# SCH_Plantcare_Module-v3_2024-10-25.net
KiCad netlist of a schematic drawn in EasyEDA
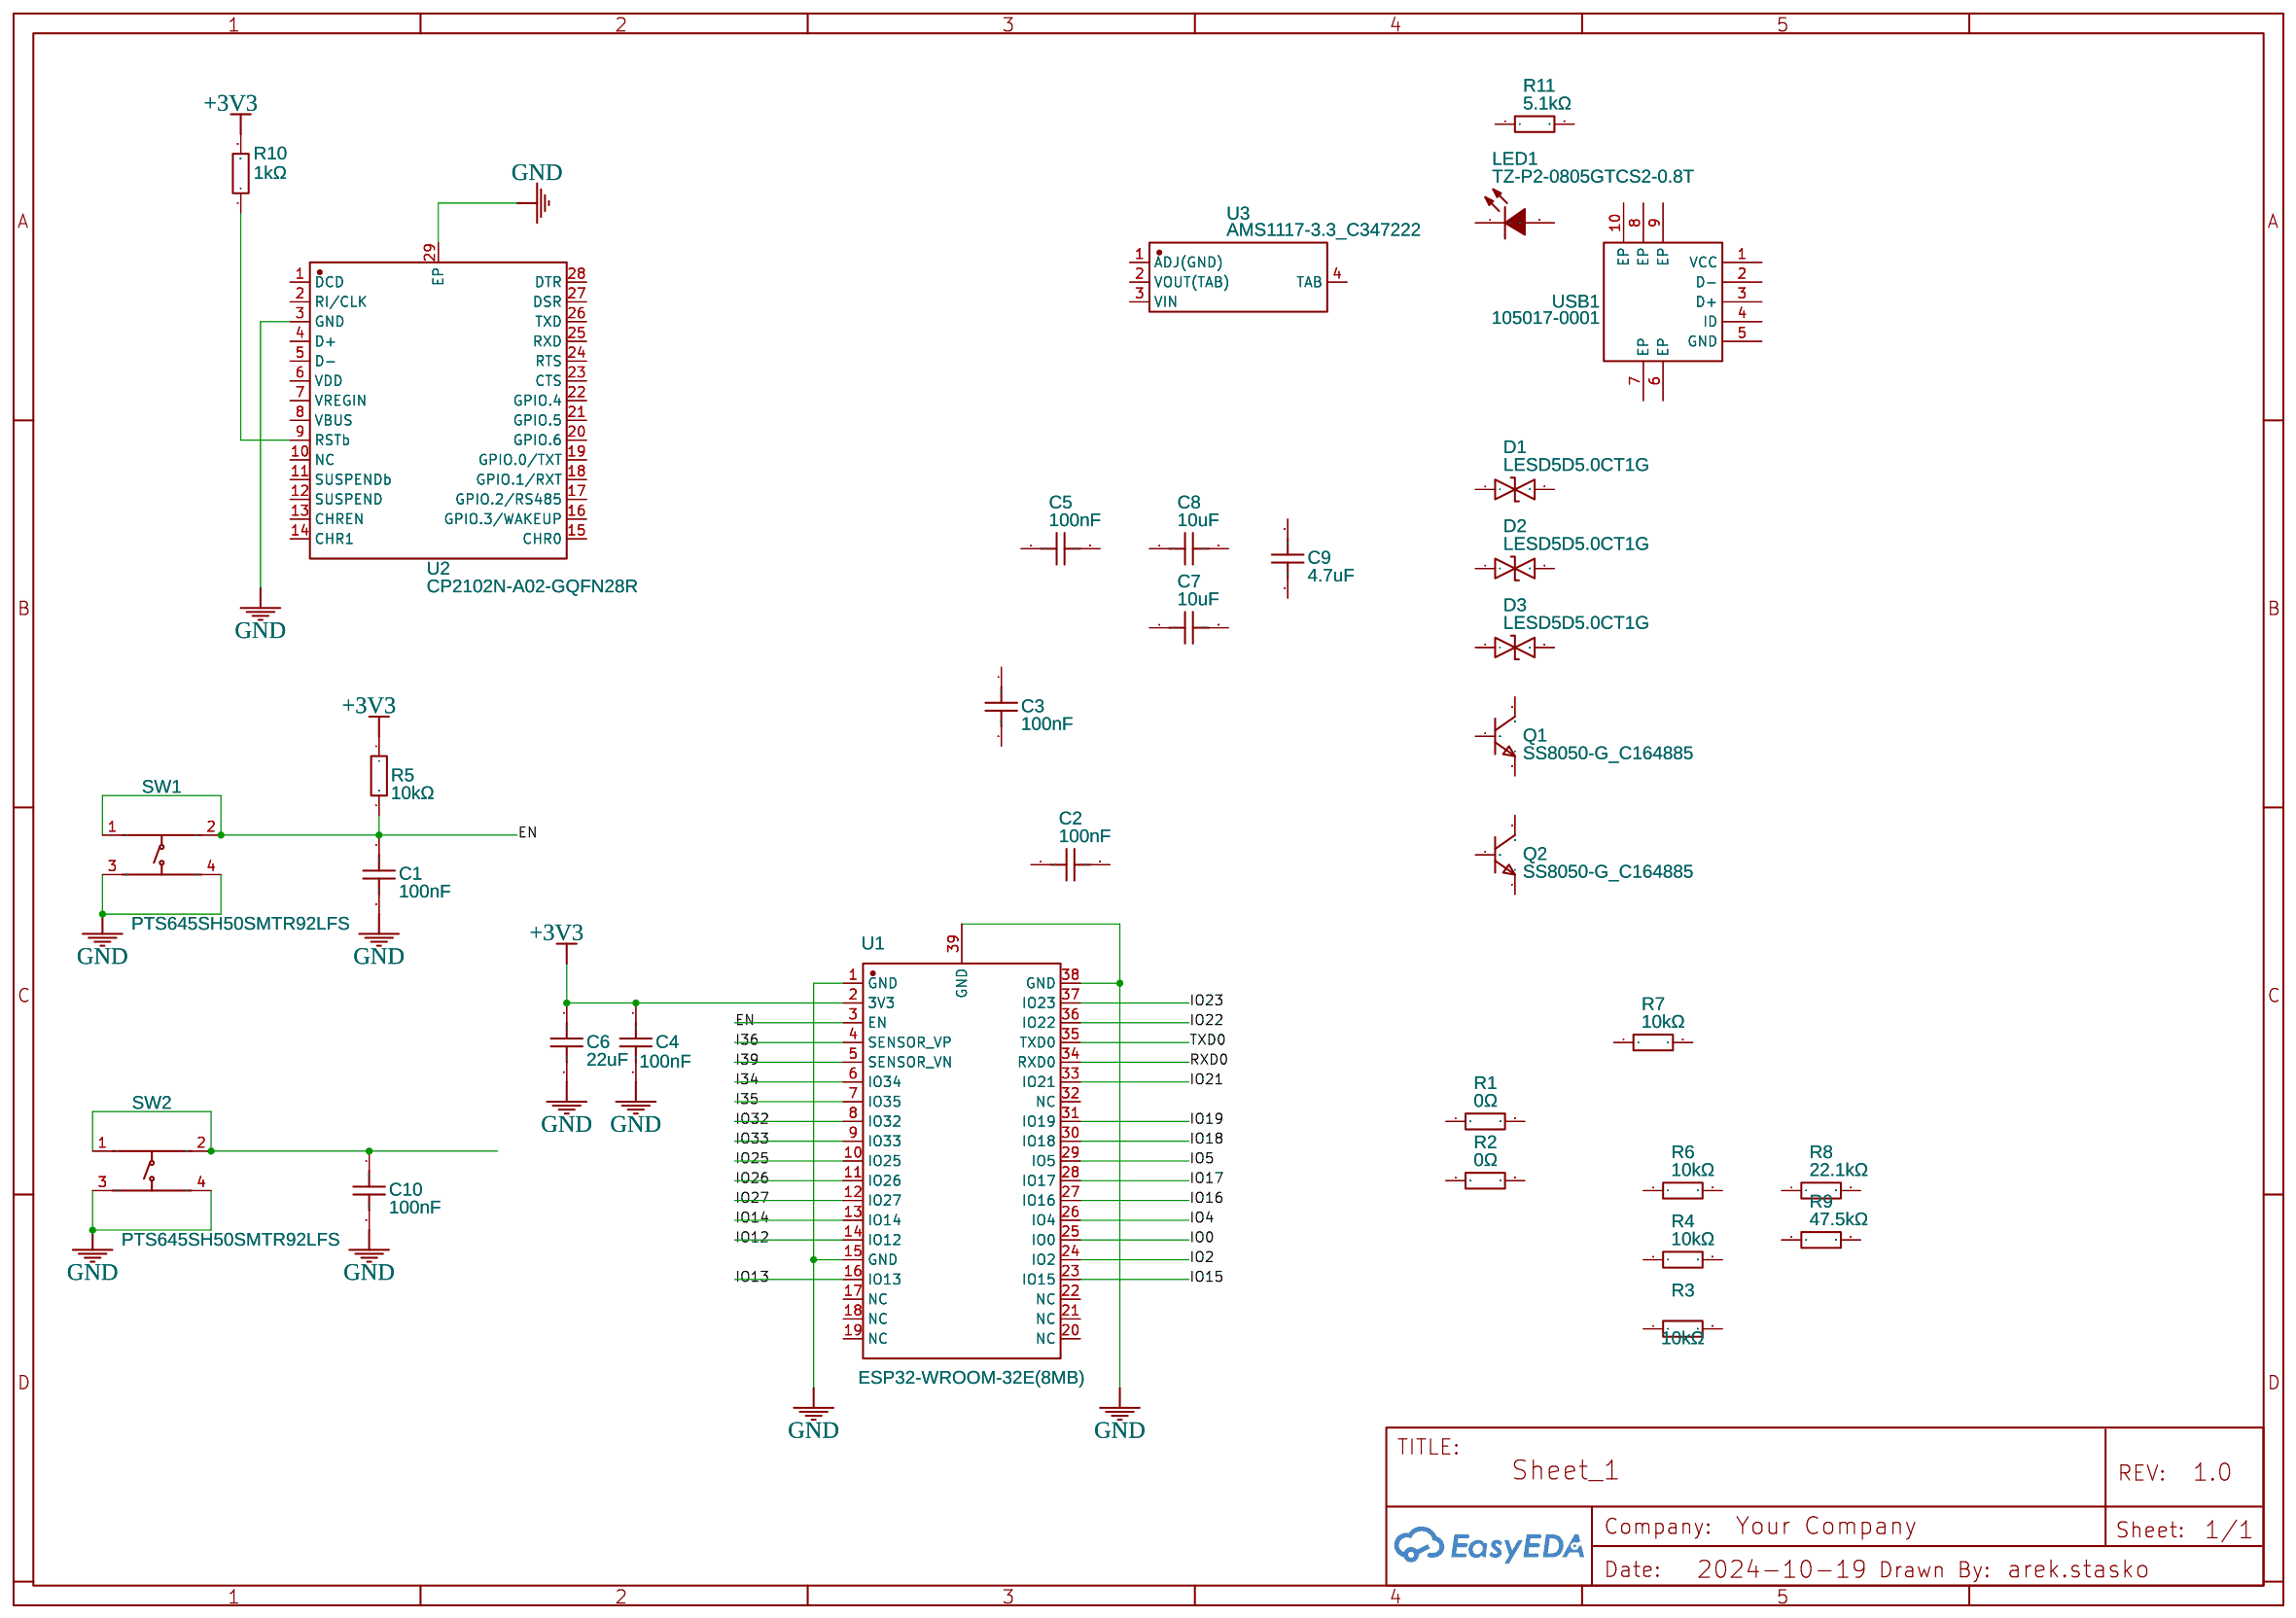
[diagram p0: schematic sheet]

(export (version "E")
  (design (tool "Eeschema 10.0.6"))
  (components
    (comp (ref "C1")
      (value "100nF")
      (fields
        (field (name "Manufacturer Part") "CL05B104KO5NNNC")
        (field (name "Manufacturer") "SAMSUNG(三星)")
      )
      (libsource (lib "") (part "CL05B104KO5NNNC_1"))
    )
    (comp (ref "C2")
      (value "100nF")
      (fields
        (field (name "Manufacturer Part") "CL05B104KO5NNNC")
        (field (name "Manufacturer") "SAMSUNG(三星)")
      )
      (libsource (lib "") (part "CL05B104KO5NNNC"))
    )
    (comp (ref "C3")
      (value "100nF")
      (fields
        (field (name "Manufacturer Part") "CL05B104KO5NNNC")
        (field (name "Manufacturer") "SAMSUNG(三星)")
      )
      (libsource (lib "") (part "CL05B104KO5NNNC_1"))
    )
    (comp (ref "C4")
      (value "100nF")
      (fields
        (field (name "Manufacturer Part") "CL05B104KO5NNNC")
        (field (name "Manufacturer") "SAMSUNG(三星)")
      )
      (libsource (lib "") (part "CL05B104KO5NNNC_1"))
    )
    (comp (ref "C5")
      (value "100nF")
      (fields
        (field (name "Manufacturer Part") "CL05B104KO5NNNC")
        (field (name "Manufacturer") "SAMSUNG(三星)")
      )
      (libsource (lib "") (part "CL05B104KO5NNNC"))
    )
    (comp (ref "C6")
      (value "22uF")
      (fields
        (field (name "Manufacturer Part") "CL21A226MAYNNNE")
        (field (name "Manufacturer") "SAMSUNG(三星)")
      )
      (libsource (lib "") (part "CL21A226MAYNNNE"))
    )
    (comp (ref "C7")
      (value "10uF")
      (fields
        (field (name "Manufacturer Part") "CL05A106MP5NUNC")
        (field (name "Manufacturer") "SAMSUNG(三星)")
      )
      (libsource (lib "") (part "CL05A106MP5NUNC_C315248"))
    )
    (comp (ref "C8")
      (value "10uF")
      (fields
        (field (name "Manufacturer Part") "CL05A106MP5NUNC")
        (field (name "Manufacturer") "SAMSUNG(三星)")
      )
      (libsource (lib "") (part "CL05A106MP5NUNC_C315248"))
    )
    (comp (ref "C9")
      (value "4.7uF")
      (fields
        (field (name "Manufacturer Part") "CL05A475KP5NRNC")
        (field (name "Manufacturer") "SAMSUNG(三星)")
      )
      (libsource (lib "") (part "CL05A475KP5NRNC"))
    )
    (comp (ref "C10")
      (value "100nF")
      (fields
        (field (name "Manufacturer Part") "CL05B104KO5NNNC")
        (field (name "Manufacturer") "SAMSUNG(三星)")
      )
      (libsource (lib "") (part "CL05B104KO5NNNC_1"))
    )
    (comp (ref "D1")
      (value "LESD5D5.0CT1G")
      (fields (field (name "Manufacturer") "LRC(乐山无线电)"))
      (libsource (lib "") (part "LESD5D5.0CT1G"))
    )
    (comp (ref "D2")
      (value "LESD5D5.0CT1G")
      (fields (field (name "Manufacturer") "LRC(乐山无线电)"))
      (libsource (lib "") (part "LESD5D5.0CT1G"))
    )
    (comp (ref "D3")
      (value "LESD5D5.0CT1G")
      (fields (field (name "Manufacturer") "LRC(乐山无线电)"))
      (libsource (lib "") (part "LESD5D5.0CT1G"))
    )
    (comp (ref "LED1")
      (value "TZ-P2-0805GTCS2-0.8T")
      (fields (field (name "Manufacturer") "TUOZHAN(拓展光电)"))
      (libsource (lib "") (part "TZ-P2-0805GTCS2-0.8T"))
    )
    (comp (ref "Q1")
      (value "SS8050-G_C164885")
      (fields (field (name "Manufacturer Part") "SS8050-G") (field (name "Manufacturer") "CJ(江苏长电/长晶)"))
      (libsource (lib "") (part "SS8050-G_C164885"))
    )
    (comp (ref "Q2")
      (value "SS8050-G_C164885")
      (fields (field (name "Manufacturer Part") "SS8050-G") (field (name "Manufacturer") "CJ(江苏长电/长晶)"))
      (libsource (lib "") (part "SS8050-G_C164885"))
    )
    (comp (ref "R1")
      (value "0Ω")
      (fields
        (field (name "Manufacturer Part") "0402WGF0000TCE")
        (field (name "Manufacturer") "UNI-ROYAL(厚声)")
      )
      (libsource (lib "") (part "0402WGF0000TCE"))
    )
    (comp (ref "R2")
      (value "0Ω")
      (fields
        (field (name "Manufacturer Part") "0402WGF0000TCE")
        (field (name "Manufacturer") "UNI-ROYAL(厚声)")
      )
      (libsource (lib "") (part "0402WGF0000TCE"))
    )
    (comp (ref "R3")
      (value "10kΩ")
      (fields
        (field (name "Manufacturer Part") "0402WGF1002TCE")
        (field (name "Manufacturer") "UNI-ROYAL(厚声)")
      )
      (libsource (lib "") (part "0402WGF1002TCE"))
    )
    (comp (ref "R4")
      (value "10kΩ")
      (fields
        (field (name "Manufacturer Part") "0402WGF1002TCE")
        (field (name "Manufacturer") "UNI-ROYAL(厚声)")
      )
      (libsource (lib "") (part "0402WGF1002TCE"))
    )
    (comp (ref "R5")
      (value "10kΩ")
      (fields
        (field (name "Manufacturer Part") "0402WGF1002TCE")
        (field (name "Manufacturer") "UNI-ROYAL(厚声)")
      )
      (libsource (lib "") (part "0402WGF1002TCE_1"))
    )
    (comp (ref "R6")
      (value "10kΩ")
      (fields
        (field (name "Manufacturer Part") "0402WGF1002TCE")
        (field (name "Manufacturer") "UNI-ROYAL(厚声)")
      )
      (libsource (lib "") (part "0402WGF1002TCE"))
    )
    (comp (ref "R7")
      (value "10kΩ")
      (fields
        (field (name "Manufacturer Part") "0402WGF1002TCE")
        (field (name "Manufacturer") "UNI-ROYAL(厚声)")
      )
      (libsource (lib "") (part "0402WGF1002TCE"))
    )
    (comp (ref "R8")
      (value "22.1kΩ")
      (fields
        (field (name "Manufacturer Part") "0402WGF2212TCE")
        (field (name "Manufacturer") "UNI-ROYAL(厚声)")
      )
      (libsource (lib "") (part "0402WGF2212TCE"))
    )
    (comp (ref "R9")
      (value "47.5kΩ")
      (fields
        (field (name "Manufacturer Part") "0402WGF4752TCE")
        (field (name "Manufacturer") "UNI-ROYAL(厚声)")
      )
      (libsource (lib "") (part "0402WGF4752TCE"))
    )
    (comp (ref "R10")
      (value "1kΩ")
      (fields
        (field (name "Manufacturer Part") "0402WGF1001TCE")
        (field (name "Manufacturer") "UNI-ROYAL(厚声)")
      )
      (libsource (lib "") (part "0402WGF1001TCE"))
    )
    (comp (ref "R11")
      (value "5.1kΩ")
      (fields
        (field (name "Manufacturer Part") "0402WGF5101TCE")
        (field (name "Manufacturer") "UNI-ROYAL(厚声)")
      )
      (libsource (lib "") (part "0402WGF5101TCE"))
    )
    (comp (ref "SW1")
      (value "PTS645SH50SMTR92LFS")
      (fields (field (name "Manufacturer") "C&K"))
      (libsource (lib "") (part "PTS645SH50SMTR92LFS"))
    )
    (comp (ref "SW2")
      (value "PTS645SH50SMTR92LFS")
      (fields (field (name "Manufacturer") "C&K"))
      (libsource (lib "") (part "PTS645SH50SMTR92LFS"))
    )
    (comp (ref "U1")
      (value "ESP32-WROOM-32E(8MB)")
      (fields
        (field (name "Manufacturer Part") "ESP32-WROOM-32E-N8")
        (field (name "Manufacturer") "ESPRESSIF(乐鑫)")
      )
      (libsource (lib "") (part "ESP32-WROOM-32E(8MB)"))
    )
    (comp (ref "U2")
      (value "CP2102N-A02-GQFN28R")
      (fields (field (name "Manufacturer") "SKYWORKS/SILICON LABS(芯科)"))
      (libsource (lib "") (part "CP2102N-A02-GQFN28R"))
    )
    (comp (ref "U3")
      (value "AMS1117-3.3_C347222")
      (fields (field (name "Manufacturer Part") "AMS1117-3.3") (field (name "Manufacturer") "UMW(友台半导体)"))
      (libsource (lib "") (part "AMS1117-3.3_C347222"))
    )
    (comp (ref "USB1")
      (value "105017-0001")
      (fields (field (name "Manufacturer Part") "1050170001") (field (name "Manufacturer") "MOLEX"))
      (libsource (lib "") (part "105017-0001"))
    )
  )
  (nets
    (net (code "1") (name "+3V3") (class "Default")
      (node (ref "C4") (pin "1") (pinfunction "1_1") (pintype "unspecified"))
      (node (ref "C6") (pin "1") (pinfunction "1_1") (pintype "unspecified"))
      (node (ref "R10") (pin "2") (pinfunction "2_2") (pintype "input"))
      (node (ref "R5") (pin "1") (pinfunction "1_1") (pintype "input"))
      (node (ref "U1") (pin "2") (pinfunction "3V3_2") (pintype "unspecified"))
    )
    (net (code "2") (name "/EN") (class "Default")
      (node (ref "C1") (pin "1") (pinfunction "1_1") (pintype "unspecified"))
      (node (ref "R5") (pin "2") (pinfunction "2_2") (pintype "input"))
      (node (ref "SW1") (pin "1") (pinfunction "1_1") (pintype "unspecified"))
      (node (ref "SW1") (pin "2") (pinfunction "2_2") (pintype "unspecified"))
      (node (ref "U1") (pin "3") (pinfunction "EN_3") (pintype "unspecified"))
    )
    (net (code "3") (name "/I34") (class "Default")
      (node (ref "U1") (pin "6") (pinfunction "IO34_6") (pintype "unspecified"))
    )
    (net (code "4") (name "/I35") (class "Default")
      (node (ref "U1") (pin "7") (pinfunction "IO35_7") (pintype "unspecified"))
    )
    (net (code "5") (name "/I36") (class "Default")
      (node (ref "U1") (pin "4") (pinfunction "SENSOR_VP_4") (pintype "unspecified"))
    )
    (net (code "6") (name "/I39") (class "Default")
      (node (ref "U1") (pin "5") (pinfunction "SENSOR_VN_5") (pintype "unspecified"))
    )
    (net (code "7") (name "/IO0") (class "Default")
      (node (ref "U1") (pin "25") (pinfunction "IO0_25") (pintype "unspecified"))
    )
    (net (code "8") (name "/IO2") (class "Default")
      (node (ref "U1") (pin "24") (pinfunction "IO2_24") (pintype "unspecified"))
    )
    (net (code "9") (name "/IO4") (class "Default")
      (node (ref "U1") (pin "26") (pinfunction "IO4_26") (pintype "unspecified"))
    )
    (net (code "10") (name "/IO5") (class "Default")
      (node (ref "U1") (pin "29") (pinfunction "IO5_29") (pintype "unspecified"))
    )
    (net (code "11") (name "/IO12") (class "Default")
      (node (ref "U1") (pin "14") (pinfunction "IO12_14") (pintype "unspecified"))
    )
    (net (code "12") (name "/IO13") (class "Default")
      (node (ref "U1") (pin "16") (pinfunction "IO13_16") (pintype "unspecified"))
    )
    (net (code "13") (name "/IO14") (class "Default")
      (node (ref "U1") (pin "13") (pinfunction "IO14_13") (pintype "unspecified"))
    )
    (net (code "14") (name "/IO15") (class "Default")
      (node (ref "U1") (pin "23") (pinfunction "IO15_23") (pintype "unspecified"))
    )
    (net (code "15") (name "/IO16") (class "Default")
      (node (ref "U1") (pin "27") (pinfunction "IO16_27") (pintype "unspecified"))
    )
    (net (code "16") (name "/IO17") (class "Default")
      (node (ref "U1") (pin "28") (pinfunction "IO17_28") (pintype "unspecified"))
    )
    (net (code "17") (name "/IO18") (class "Default")
      (node (ref "U1") (pin "30") (pinfunction "IO18_30") (pintype "unspecified"))
    )
    (net (code "18") (name "/IO19") (class "Default")
      (node (ref "U1") (pin "31") (pinfunction "IO19_31") (pintype "unspecified"))
    )
    (net (code "19") (name "/IO21") (class "Default")
      (node (ref "U1") (pin "33") (pinfunction "IO21_33") (pintype "unspecified"))
    )
    (net (code "20") (name "/IO22") (class "Default")
      (node (ref "U1") (pin "36") (pinfunction "IO22_36") (pintype "unspecified"))
    )
    (net (code "21") (name "/IO23") (class "Default")
      (node (ref "U1") (pin "37") (pinfunction "IO23_37") (pintype "unspecified"))
    )
    (net (code "22") (name "/IO25") (class "Default")
      (node (ref "U1") (pin "10") (pinfunction "IO25_10") (pintype "unspecified"))
    )
    (net (code "23") (name "/IO26") (class "Default")
      (node (ref "U1") (pin "11") (pinfunction "IO26_11") (pintype "unspecified"))
    )
    (net (code "24") (name "/IO27") (class "Default")
      (node (ref "U1") (pin "12") (pinfunction "IO27_12") (pintype "unspecified"))
    )
    (net (code "25") (name "/IO32") (class "Default")
      (node (ref "U1") (pin "8") (pinfunction "IO32_8") (pintype "unspecified"))
    )
    (net (code "26") (name "/IO33") (class "Default")
      (node (ref "U1") (pin "9") (pinfunction "IO33_9") (pintype "unspecified"))
    )
    (net (code "27") (name "/RXD0") (class "Default")
      (node (ref "U1") (pin "34") (pinfunction "RXD0_34") (pintype "unspecified"))
    )
    (net (code "28") (name "/TXD0") (class "Default")
      (node (ref "U1") (pin "35") (pinfunction "TXD0_35") (pintype "unspecified"))
    )
    (net (code "29") (name "GND") (class "Default")
      (node (ref "C1") (pin "2") (pinfunction "2_2") (pintype "unspecified"))
      (node (ref "C10") (pin "2") (pinfunction "2_2") (pintype "unspecified"))
      (node (ref "C4") (pin "2") (pinfunction "2_2") (pintype "unspecified"))
      (node (ref "C6") (pin "2") (pinfunction "2_2") (pintype "unspecified"))
      (node (ref "SW1") (pin "3") (pinfunction "3_3") (pintype "unspecified"))
      (node (ref "SW1") (pin "4") (pinfunction "4_4") (pintype "unspecified"))
      (node (ref "SW2") (pin "3") (pinfunction "3_3") (pintype "unspecified"))
      (node (ref "SW2") (pin "4") (pinfunction "4_4") (pintype "unspecified"))
      (node (ref "U1") (pin "1") (pinfunction "GND_1") (pintype "unspecified"))
      (node (ref "U1") (pin "15") (pinfunction "GND_15") (pintype "unspecified"))
      (node (ref "U1") (pin "38") (pinfunction "GND_38") (pintype "unspecified"))
      (node (ref "U1") (pin "39") (pinfunction "GND_39") (pintype "unspecified"))
      (node (ref "U2") (pin "29") (pinfunction "EP_29") (pintype "unspecified"))
      (node (ref "U2") (pin "3") (pinfunction "GND_3") (pintype "unspecified"))
    )
    (net (code "30") (name "Net-(C10-Pad1)") (class "Default")
      (node (ref "C10") (pin "1") (pinfunction "1_1") (pintype "unspecified"))
      (node (ref "SW2") (pin "1") (pinfunction "1_1") (pintype "unspecified"))
      (node (ref "SW2") (pin "2") (pinfunction "2_2") (pintype "unspecified"))
    )
    (net (code "31") (name "Net-(U2-RSTb)") (class "Default")
      (node (ref "R10") (pin "1") (pinfunction "1_1") (pintype "input"))
      (node (ref "U2") (pin "9") (pinfunction "RSTb_9") (pintype "unspecified"))
    )
    (net (code "32") (name "unconnected-(C2-Pad1)") (class "Default")
      (node (ref "C2") (pin "1") (pinfunction "1_1") (pintype "unspecified"))
    )
    (net (code "33") (name "unconnected-(C2-Pad2)") (class "Default")
      (node (ref "C2") (pin "2") (pinfunction "2_2") (pintype "unspecified"))
    )
    (net (code "34") (name "unconnected-(C3-Pad1)") (class "Default")
      (node (ref "C3") (pin "1") (pinfunction "1_1") (pintype "unspecified"))
    )
    (net (code "35") (name "unconnected-(C3-Pad2)") (class "Default")
      (node (ref "C3") (pin "2") (pinfunction "2_2") (pintype "unspecified"))
    )
    (net (code "36") (name "unconnected-(C5-Pad1)") (class "Default")
      (node (ref "C5") (pin "1") (pinfunction "1_1") (pintype "unspecified"))
    )
    (net (code "37") (name "unconnected-(C5-Pad2)") (class "Default")
      (node (ref "C5") (pin "2") (pinfunction "2_2") (pintype "unspecified"))
    )
    (net (code "38") (name "unconnected-(C7-Pad1)") (class "Default")
      (node (ref "C7") (pin "1") (pinfunction "1_1") (pintype "unspecified"))
    )
    (net (code "39") (name "unconnected-(C7-Pad2)") (class "Default")
      (node (ref "C7") (pin "2") (pinfunction "2_2") (pintype "unspecified"))
    )
    (net (code "40") (name "unconnected-(C8-Pad1)") (class "Default")
      (node (ref "C8") (pin "1") (pinfunction "1_1") (pintype "unspecified"))
    )
    (net (code "41") (name "unconnected-(C8-Pad2)") (class "Default")
      (node (ref "C8") (pin "2") (pinfunction "2_2") (pintype "unspecified"))
    )
    (net (code "42") (name "unconnected-(C9-Pad1)") (class "Default")
      (node (ref "C9") (pin "1") (pinfunction "1_1") (pintype "unspecified"))
    )
    (net (code "43") (name "unconnected-(C9-Pad2)") (class "Default")
      (node (ref "C9") (pin "2") (pinfunction "2_2") (pintype "unspecified"))
    )
    (net (code "44") (name "unconnected-(D1-Pad1)") (class "Default")
      (node (ref "D1") (pin "1") (pinfunction "1_1") (pintype "unspecified"))
    )
    (net (code "45") (name "unconnected-(D1-Pad2)") (class "Default")
      (node (ref "D1") (pin "2") (pinfunction "2_2") (pintype "unspecified"))
    )
    (net (code "46") (name "unconnected-(D2-Pad1)") (class "Default")
      (node (ref "D2") (pin "1") (pinfunction "1_1") (pintype "unspecified"))
    )
    (net (code "47") (name "unconnected-(D2-Pad2)") (class "Default")
      (node (ref "D2") (pin "2") (pinfunction "2_2") (pintype "unspecified"))
    )
    (net (code "48") (name "unconnected-(D3-Pad1)") (class "Default")
      (node (ref "D3") (pin "1") (pinfunction "1_1") (pintype "unspecified"))
    )
    (net (code "49") (name "unconnected-(D3-Pad2)") (class "Default")
      (node (ref "D3") (pin "2") (pinfunction "2_2") (pintype "unspecified"))
    )
    (net (code "50") (name "unconnected-(LED1-+-Pad2)") (class "Default")
      (node (ref "LED1") (pin "2") (pinfunction "+_2") (pintype "unspecified"))
    )
    (net (code "51") (name "unconnected-(LED1---Pad1)") (class "Default")
      (node (ref "LED1") (pin "1") (pinfunction "-_1") (pintype "unspecified"))
    )
    (net (code "52") (name "unconnected-(Q1-B-Pad1)") (class "Default")
      (node (ref "Q1") (pin "1") (pinfunction "B_1") (pintype "unspecified"))
    )
    (net (code "53") (name "unconnected-(Q1-C-Pad3)") (class "Default")
      (node (ref "Q1") (pin "3") (pinfunction "C_3") (pintype "unspecified"))
    )
    (net (code "54") (name "unconnected-(Q1-E-Pad2)") (class "Default")
      (node (ref "Q1") (pin "2") (pinfunction "E_2") (pintype "unspecified"))
    )
    (net (code "55") (name "unconnected-(Q2-B-Pad1)") (class "Default")
      (node (ref "Q2") (pin "1") (pinfunction "B_1") (pintype "unspecified"))
    )
    (net (code "56") (name "unconnected-(Q2-C-Pad3)") (class "Default")
      (node (ref "Q2") (pin "3") (pinfunction "C_3") (pintype "unspecified"))
    )
    (net (code "57") (name "unconnected-(Q2-E-Pad2)") (class "Default")
      (node (ref "Q2") (pin "2") (pinfunction "E_2") (pintype "unspecified"))
    )
    (net (code "58") (name "unconnected-(R1-Pad1)") (class "Default")
      (node (ref "R1") (pin "1") (pinfunction "1_1") (pintype "input"))
    )
    (net (code "59") (name "unconnected-(R1-Pad2)") (class "Default")
      (node (ref "R1") (pin "2") (pinfunction "2_2") (pintype "input"))
    )
    (net (code "60") (name "unconnected-(R2-Pad1)") (class "Default")
      (node (ref "R2") (pin "1") (pinfunction "1_1") (pintype "input"))
    )
    (net (code "61") (name "unconnected-(R2-Pad2)") (class "Default")
      (node (ref "R2") (pin "2") (pinfunction "2_2") (pintype "input"))
    )
    (net (code "62") (name "unconnected-(R3-Pad1)") (class "Default")
      (node (ref "R3") (pin "1") (pinfunction "1_1") (pintype "input"))
    )
    (net (code "63") (name "unconnected-(R3-Pad2)") (class "Default")
      (node (ref "R3") (pin "2") (pinfunction "2_2") (pintype "input"))
    )
    (net (code "64") (name "unconnected-(R4-Pad1)") (class "Default")
      (node (ref "R4") (pin "1") (pinfunction "1_1") (pintype "input"))
    )
    (net (code "65") (name "unconnected-(R4-Pad2)") (class "Default")
      (node (ref "R4") (pin "2") (pinfunction "2_2") (pintype "input"))
    )
    (net (code "66") (name "unconnected-(R6-Pad1)") (class "Default")
      (node (ref "R6") (pin "1") (pinfunction "1_1") (pintype "input"))
    )
    (net (code "67") (name "unconnected-(R6-Pad2)") (class "Default")
      (node (ref "R6") (pin "2") (pinfunction "2_2") (pintype "input"))
    )
    (net (code "68") (name "unconnected-(R7-Pad1)") (class "Default")
      (node (ref "R7") (pin "1") (pinfunction "1_1") (pintype "input"))
    )
    (net (code "69") (name "unconnected-(R7-Pad2)") (class "Default")
      (node (ref "R7") (pin "2") (pinfunction "2_2") (pintype "input"))
    )
    (net (code "70") (name "unconnected-(R8-Pad1)") (class "Default")
      (node (ref "R8") (pin "1") (pinfunction "1_1") (pintype "input"))
    )
    (net (code "71") (name "unconnected-(R8-Pad2)") (class "Default")
      (node (ref "R8") (pin "2") (pinfunction "2_2") (pintype "input"))
    )
    (net (code "72") (name "unconnected-(R9-Pad1)") (class "Default")
      (node (ref "R9") (pin "1") (pinfunction "1_1") (pintype "input"))
    )
    (net (code "73") (name "unconnected-(R9-Pad2)") (class "Default")
      (node (ref "R9") (pin "2") (pinfunction "2_2") (pintype "input"))
    )
    (net (code "74") (name "unconnected-(R11-Pad1)") (class "Default")
      (node (ref "R11") (pin "1") (pinfunction "1_1") (pintype "input"))
    )
    (net (code "75") (name "unconnected-(R11-Pad2)") (class "Default")
      (node (ref "R11") (pin "2") (pinfunction "2_2") (pintype "input"))
    )
    (net (code "76") (name "unconnected-(U1-NC-Pad17)") (class "Default")
      (node (ref "U1") (pin "17") (pinfunction "NC_17") (pintype "unspecified"))
    )
    (net (code "77") (name "unconnected-(U1-NC-Pad18)") (class "Default")
      (node (ref "U1") (pin "18") (pinfunction "NC_18") (pintype "unspecified"))
    )
    (net (code "78") (name "unconnected-(U1-NC-Pad19)") (class "Default")
      (node (ref "U1") (pin "19") (pinfunction "NC_19") (pintype "unspecified"))
    )
    (net (code "79") (name "unconnected-(U1-NC-Pad20)") (class "Default")
      (node (ref "U1") (pin "20") (pinfunction "NC_20") (pintype "unspecified"))
    )
    (net (code "80") (name "unconnected-(U1-NC-Pad21)") (class "Default")
      (node (ref "U1") (pin "21") (pinfunction "NC_21") (pintype "unspecified"))
    )
    (net (code "81") (name "unconnected-(U1-NC-Pad22)") (class "Default")
      (node (ref "U1") (pin "22") (pinfunction "NC_22") (pintype "unspecified"))
    )
    (net (code "82") (name "unconnected-(U1-NC-Pad32)") (class "Default")
      (node (ref "U1") (pin "32") (pinfunction "NC_32") (pintype "unspecified"))
    )
    (net (code "83") (name "unconnected-(U2-CHR0-Pad15)") (class "Default")
      (node (ref "U2") (pin "15") (pinfunction "CHR0_15") (pintype "unspecified"))
    )
    (net (code "84") (name "unconnected-(U2-CHR1-Pad14)") (class "Default")
      (node (ref "U2") (pin "14") (pinfunction "CHR1_14") (pintype "unspecified"))
    )
    (net (code "85") (name "unconnected-(U2-CHREN-Pad13)") (class "Default")
      (node (ref "U2") (pin "13") (pinfunction "CHREN_13") (pintype "unspecified"))
    )
    (net (code "86") (name "unconnected-(U2-CTS-Pad23)") (class "Default")
      (node (ref "U2") (pin "23") (pinfunction "CTS_23") (pintype "unspecified"))
    )
    (net (code "87") (name "unconnected-(U2-D+-Pad4)") (class "Default")
      (node (ref "U2") (pin "4") (pinfunction "D+_4") (pintype "unspecified"))
    )
    (net (code "88") (name "unconnected-(U2-D--Pad5)") (class "Default")
      (node (ref "U2") (pin "5") (pinfunction "D-_5") (pintype "unspecified"))
    )
    (net (code "89") (name "unconnected-(U2-DCD-Pad1)") (class "Default")
      (node (ref "U2") (pin "1") (pinfunction "DCD_1") (pintype "unspecified"))
    )
    (net (code "90") (name "unconnected-(U2-DSR-Pad27)") (class "Default")
      (node (ref "U2") (pin "27") (pinfunction "DSR_27") (pintype "unspecified"))
    )
    (net (code "91") (name "unconnected-(U2-DTR-Pad28)") (class "Default")
      (node (ref "U2") (pin "28") (pinfunction "DTR_28") (pintype "unspecified"))
    )
    (net (code "92") (name "unconnected-(U2-GPIO.0{slash}TXT-Pad19)") (class "Default")
      (node (ref "U2") (pin "19") (pinfunction "GPIO.0/TXT_19") (pintype "unspecified"))
    )
    (net (code "93") (name "unconnected-(U2-GPIO.1{slash}RXT-Pad18)") (class "Default")
      (node (ref "U2") (pin "18") (pinfunction "GPIO.1/RXT_18") (pintype "unspecified"))
    )
    (net (code "94") (name "unconnected-(U2-GPIO.2{slash}RS485-Pad17)") (class "Default")
      (node (ref "U2") (pin "17") (pinfunction "GPIO.2/RS485_17") (pintype "unspecified"))
    )
    (net (code "95") (name "unconnected-(U2-GPIO.3{slash}WAKEUP-Pad16)") (class "Default")
      (node (ref "U2") (pin "16") (pinfunction "GPIO.3/WAKEUP_16") (pintype "unspecified"))
    )
    (net (code "96") (name "unconnected-(U2-GPIO.4-Pad22)") (class "Default")
      (node (ref "U2") (pin "22") (pinfunction "GPIO.4_22") (pintype "unspecified"))
    )
    (net (code "97") (name "unconnected-(U2-GPIO.5-Pad21)") (class "Default")
      (node (ref "U2") (pin "21") (pinfunction "GPIO.5_21") (pintype "unspecified"))
    )
    (net (code "98") (name "unconnected-(U2-GPIO.6-Pad20)") (class "Default")
      (node (ref "U2") (pin "20") (pinfunction "GPIO.6_20") (pintype "unspecified"))
    )
    (net (code "99") (name "unconnected-(U2-NC-Pad10)") (class "Default")
      (node (ref "U2") (pin "10") (pinfunction "NC_10") (pintype "unspecified"))
    )
    (net (code "100") (name "unconnected-(U2-RI{slash}CLK-Pad2)") (class "Default")
      (node (ref "U2") (pin "2") (pinfunction "RI/CLK_2") (pintype "unspecified"))
    )
    (net (code "101") (name "unconnected-(U2-RTS-Pad24)") (class "Default")
      (node (ref "U2") (pin "24") (pinfunction "RTS_24") (pintype "unspecified"))
    )
    (net (code "102") (name "unconnected-(U2-RXD-Pad25)") (class "Default")
      (node (ref "U2") (pin "25") (pinfunction "RXD_25") (pintype "unspecified"))
    )
    (net (code "103") (name "unconnected-(U2-SUSPEND-Pad12)") (class "Default")
      (node (ref "U2") (pin "12") (pinfunction "SUSPEND_12") (pintype "unspecified"))
    )
    (net (code "104") (name "unconnected-(U2-SUSPENDb-Pad11)") (class "Default")
      (node (ref "U2") (pin "11") (pinfunction "SUSPENDb_11") (pintype "unspecified"))
    )
    (net (code "105") (name "unconnected-(U2-TXD-Pad26)") (class "Default")
      (node (ref "U2") (pin "26") (pinfunction "TXD_26") (pintype "unspecified"))
    )
    (net (code "106") (name "unconnected-(U2-VBUS-Pad8)") (class "Default")
      (node (ref "U2") (pin "8") (pinfunction "VBUS_8") (pintype "unspecified"))
    )
    (net (code "107") (name "unconnected-(U2-VDD-Pad6)") (class "Default")
      (node (ref "U2") (pin "6") (pinfunction "VDD_6") (pintype "unspecified"))
    )
    (net (code "108") (name "unconnected-(U2-VREGIN-Pad7)") (class "Default")
      (node (ref "U2") (pin "7") (pinfunction "VREGIN_7") (pintype "unspecified"))
    )
    (net (code "109") (name "unconnected-(U3-ADJ(GND)-Pad1)") (class "Default")
      (node (ref "U3") (pin "1") (pinfunction "ADJ(GND)_1") (pintype "unspecified"))
    )
    (net (code "110") (name "unconnected-(U3-TAB-Pad4)") (class "Default")
      (node (ref "U3") (pin "4") (pinfunction "TAB_4") (pintype "unspecified"))
    )
    (net (code "111") (name "unconnected-(U3-VIN-Pad3)") (class "Default")
      (node (ref "U3") (pin "3") (pinfunction "VIN_3") (pintype "unspecified"))
    )
    (net (code "112") (name "unconnected-(U3-VOUT(TAB)-Pad2)") (class "Default")
      (node (ref "U3") (pin "2") (pinfunction "VOUT(TAB)_2") (pintype "unspecified"))
    )
    (net (code "113") (name "unconnected-(USB1-D+-Pad3)") (class "Default")
      (node (ref "USB1") (pin "3") (pinfunction "D+_3") (pintype "unspecified"))
    )
    (net (code "114") (name "unconnected-(USB1-D--Pad2)") (class "Default")
      (node (ref "USB1") (pin "2") (pinfunction "D-_2") (pintype "unspecified"))
    )
    (net (code "115") (name "unconnected-(USB1-EP-Pad6)") (class "Default")
      (node (ref "USB1") (pin "6") (pinfunction "EP_6") (pintype "unspecified"))
    )
    (net (code "116") (name "unconnected-(USB1-EP-Pad7)") (class "Default")
      (node (ref "USB1") (pin "7") (pinfunction "EP_7") (pintype "unspecified"))
    )
    (net (code "117") (name "unconnected-(USB1-EP-Pad8)") (class "Default")
      (node (ref "USB1") (pin "8") (pinfunction "EP_8") (pintype "unspecified"))
    )
    (net (code "118") (name "unconnected-(USB1-EP-Pad9)") (class "Default")
      (node (ref "USB1") (pin "9") (pinfunction "EP_9") (pintype "unspecified"))
    )
    (net (code "119") (name "unconnected-(USB1-EP-Pad10)") (class "Default")
      (node (ref "USB1") (pin "10") (pinfunction "EP_10") (pintype "unspecified"))
    )
    (net (code "120") (name "unconnected-(USB1-GND-Pad5)") (class "Default")
      (node (ref "USB1") (pin "5") (pinfunction "GND_5") (pintype "unspecified"))
    )
    (net (code "121") (name "unconnected-(USB1-ID-Pad4)") (class "Default")
      (node (ref "USB1") (pin "4") (pinfunction "ID_4") (pintype "unspecified"))
    )
    (net (code "122") (name "unconnected-(USB1-VCC-Pad1)") (class "Default")
      (node (ref "USB1") (pin "1") (pinfunction "VCC_1") (pintype "unspecified"))
    )
  )
)
